# Divider9.net
KiCad netlist of a schematic drawn in Altium Designer
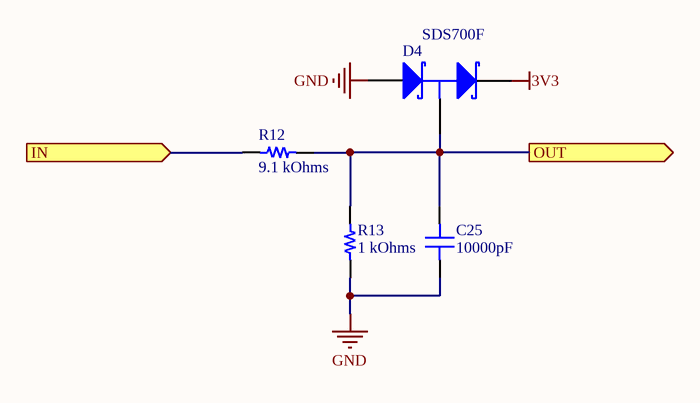
[diagram p0: Divider9.SchDoc]

(export (version "E")
  (design (tool "Eeschema 10.0.6"))
  (components
    (comp (ref "C25")
      (value "10000pF")
      (footprint "CAP 0805_2012")
      (description "CAP CER 0805 10NF 500V X7R 10%")
      (fields (field (name "PART NUMBER") "C0805C103KCRACAUTO") (field (name "MANUFACTURER") "KEMET"))
      (libsource (lib "Celestial Altium Library - altium_library") (part "Capacitor"))
    )
    (comp (ref "D4")
      (value "SDS700F")
      (footprint "SOT323_N")
      (description "Schottky Barrier Double Diode")
      (fields (field (name "PUBLISHER") "Altium Limited"))
      (libsource (lib "Philips Discrete Diode - Schottky") (part "BAT854SW"))
    )
    (comp (ref "R12")
      (value "9.1 kOhms")
      (footprint "RES 0805_2012")
      (description "RES SMD 9.1K OHM 1% 1/8W 0805")
      (fields (field (name "PART NUMBER") "CR0805-FX-9101ELF") (field (name "MANUFACTURER") "Bourns Inc."))
      (libsource (lib "Celestial Altium Library - altium_library") (part "Resistor"))
    )
    (comp (ref "R13")
      (value "1 kOhms")
      (footprint "RES 0805_2012")
      (description "RES SMD 1K OHM 1% 0.4W 0805")
      (fields (field (name "PART NUMBER") "ESR10EZPF1001") (field (name "MANUFACTURER") "Rohm Semiconductor"))
      (libsource (lib "Celestial Altium Library - altium_library") (part "Resistor"))
    )
  )
  (nets
    (net (code "1") (name "/IN") (class "Default")
      (node (ref "R12") (pin "1") (pinfunction "1_1") (pintype "passive"))
    )
    (net (code "2") (name "/OUT") (class "Default")
      (node (ref "C25") (pin "2") (pinfunction "2_2") (pintype "passive"))
      (node (ref "D4") (pin "3") (pinfunction "C_3") (pintype "passive"))
      (node (ref "R12") (pin "2") (pinfunction "2_2") (pintype "passive"))
      (node (ref "R13") (pin "2") (pinfunction "2_2") (pintype "passive"))
    )
    (net (code "3") (name "3V3") (class "Default")
      (node (ref "D4") (pin "2") (pinfunction "K_2") (pintype "passive"))
    )
    (net (code "4") (name "GND") (class "Default")
      (node (ref "C25") (pin "1") (pinfunction "1_1") (pintype "passive"))
      (node (ref "D4") (pin "1") (pinfunction "A_1") (pintype "passive"))
      (node (ref "R13") (pin "1") (pinfunction "1_1") (pintype "passive"))
    )
  )
)
